# schematic.net
KiCad netlist of a schematic drawn in EasyEDA
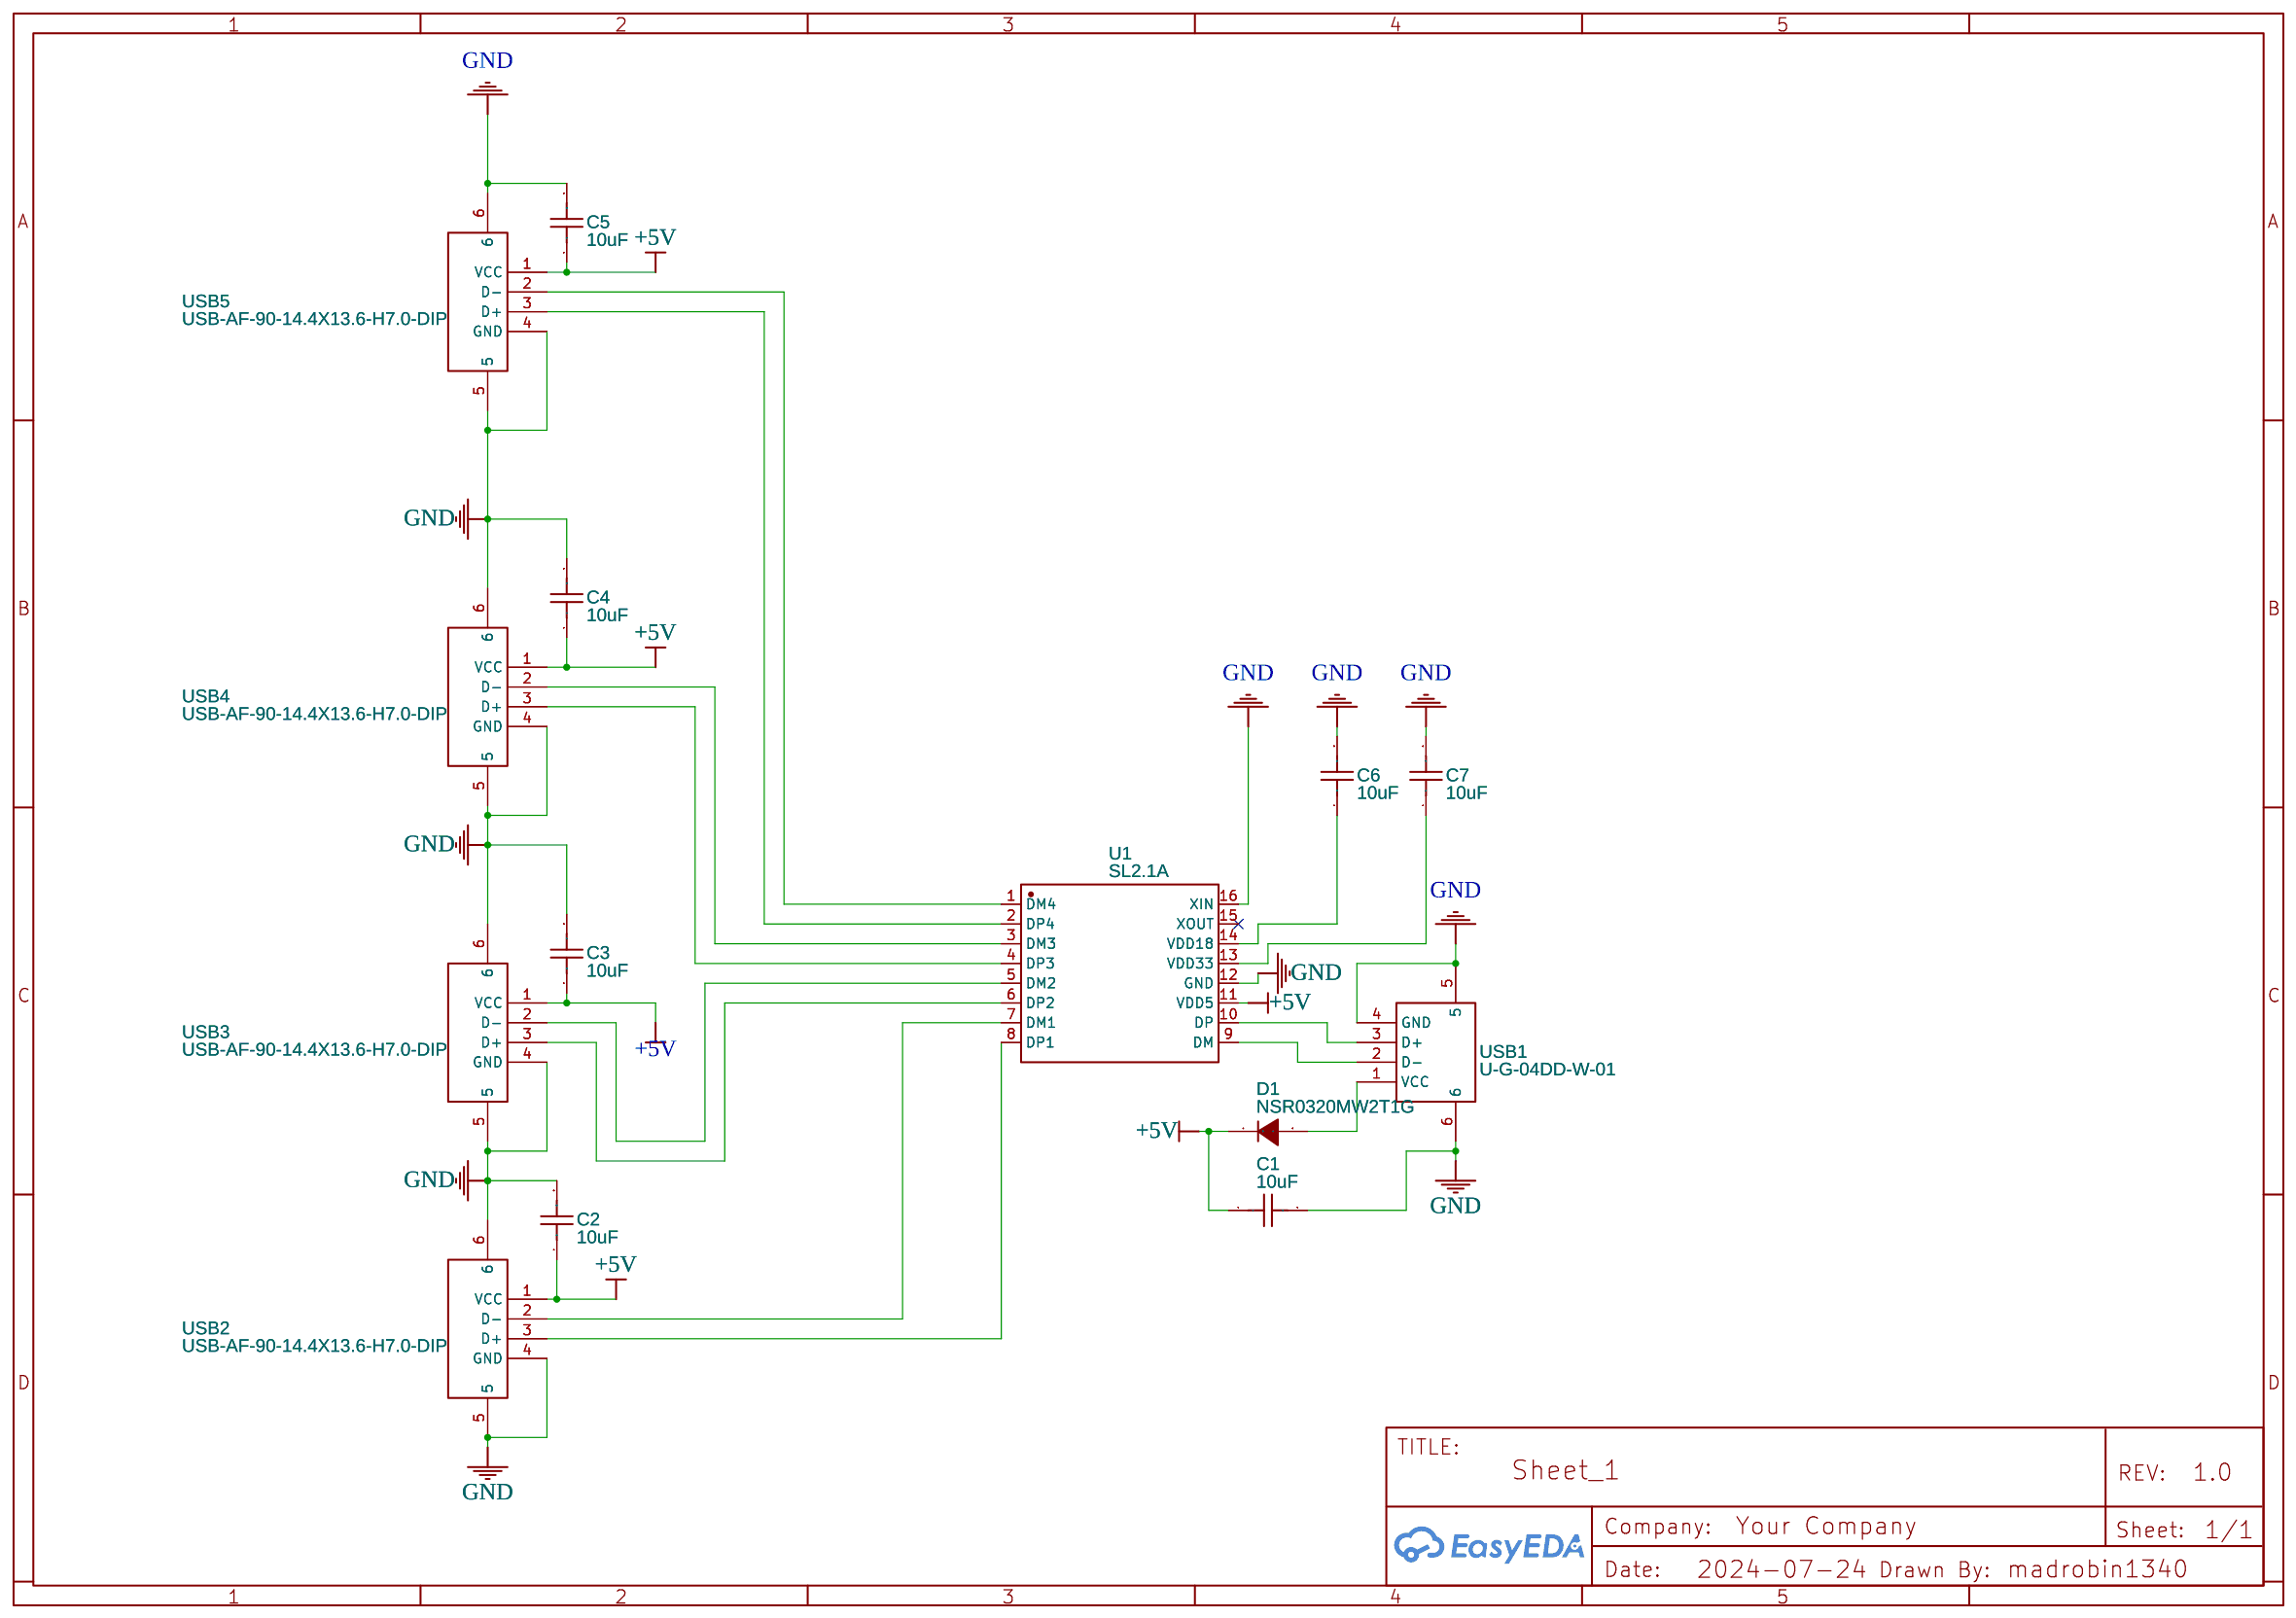
[diagram p0: schematic sheet]

(export (version "E")
  (design (tool "Eeschema 10.0.6"))
  (components
    (comp (ref "C1")
      (value "10uF")
      (fields
        (field (name "Manufacturer Part") "CL10A106KP8NNNC")
        (field (name "Manufacturer") "SAMSUNG(三星)")
      )
      (libsource (lib "") (part "CL10A106KP8NNNC_1"))
    )
    (comp (ref "C2")
      (value "10uF")
      (fields
        (field (name "Manufacturer Part") "CL10A106KP8NNNC")
        (field (name "Manufacturer") "SAMSUNG(三星)")
      )
      (libsource (lib "") (part "CL10A106KP8NNNC"))
    )
    (comp (ref "C3")
      (value "10uF")
      (fields
        (field (name "Manufacturer Part") "CL10A106KP8NNNC")
        (field (name "Manufacturer") "SAMSUNG(三星)")
      )
      (libsource (lib "") (part "CL10A106KP8NNNC"))
    )
    (comp (ref "C4")
      (value "10uF")
      (fields
        (field (name "Manufacturer Part") "CL10A106KP8NNNC")
        (field (name "Manufacturer") "SAMSUNG(三星)")
      )
      (libsource (lib "") (part "CL10A106KP8NNNC"))
    )
    (comp (ref "C5")
      (value "10uF")
      (fields
        (field (name "Manufacturer Part") "CL10A106KP8NNNC")
        (field (name "Manufacturer") "SAMSUNG(三星)")
      )
      (libsource (lib "") (part "CL10A106KP8NNNC"))
    )
    (comp (ref "C6")
      (value "10uF")
      (fields
        (field (name "Manufacturer Part") "CL10A106KP8NNNC")
        (field (name "Manufacturer") "SAMSUNG(三星)")
      )
      (libsource (lib "") (part "CL10A106KP8NNNC"))
    )
    (comp (ref "C7")
      (value "10uF")
      (fields
        (field (name "Manufacturer Part") "CL10A106KP8NNNC")
        (field (name "Manufacturer") "SAMSUNG(三星)")
      )
      (libsource (lib "") (part "CL10A106KP8NNNC"))
    )
    (comp (ref "D1")
      (value "NSR0320MW2T1G")
      (fields (field (name "Manufacturer") "onsemi(安森美)"))
      (libsource (lib "") (part "NSR0320MW2T1G"))
    )
    (comp (ref "U1")
      (value "SL2.1A")
      (fields (field (name "Manufacturer") "CoreChips(和芯润德)"))
      (libsource (lib "") (part "SL2.1A"))
    )
    (comp (ref "USB1")
      (value "U-G-04DD-W-01")
      (fields (field (name "Manufacturer Part") "U-G-O4DD-W-1") (field (name "Manufacturer") "韩国韩荣"))
      (libsource (lib "") (part "U-G-04DD-W-01"))
    )
    (comp (ref "USB2")
      (value "USB-AF-90-14.4X13.6-H7.0-DIP")
      (fields (field (name "Manufacturer Part") "903-131A1011D10100") (field (name "Manufacturer") "精拓金"))
      (libsource (lib "") (part "USB-AF-90-14.4X13.6-H7.0-DIP"))
    )
    (comp (ref "USB3")
      (value "USB-AF-90-14.4X13.6-H7.0-DIP")
      (fields (field (name "Manufacturer Part") "903-131A1011D10100") (field (name "Manufacturer") "精拓金"))
      (libsource (lib "") (part "USB-AF-90-14.4X13.6-H7.0-DIP"))
    )
    (comp (ref "USB4")
      (value "USB-AF-90-14.4X13.6-H7.0-DIP")
      (fields (field (name "Manufacturer Part") "903-131A1011D10100") (field (name "Manufacturer") "精拓金"))
      (libsource (lib "") (part "USB-AF-90-14.4X13.6-H7.0-DIP"))
    )
    (comp (ref "USB5")
      (value "USB-AF-90-14.4X13.6-H7.0-DIP")
      (fields (field (name "Manufacturer Part") "903-131A1011D10100") (field (name "Manufacturer") "精拓金"))
      (libsource (lib "") (part "USB-AF-90-14.4X13.6-H7.0-DIP"))
    )
  )
  (nets
    (net (code "1") (name "+5V") (class "Default")
      (node (ref "C1") (pin "1") (pinfunction "1_1") (pintype "unspecified"))
      (node (ref "C2") (pin "1") (pinfunction "1_1") (pintype "unspecified"))
      (node (ref "C3") (pin "1") (pinfunction "1_1") (pintype "unspecified"))
      (node (ref "C4") (pin "1") (pinfunction "1_1") (pintype "unspecified"))
      (node (ref "C5") (pin "1") (pinfunction "1_1") (pintype "unspecified"))
      (node (ref "D1") (pin "1") (pinfunction "C_1") (pintype "unspecified"))
      (node (ref "U1") (pin "11") (pinfunction "VDD5_11") (pintype "unspecified"))
      (node (ref "USB2") (pin "1") (pinfunction "VCC_1") (pintype "unspecified"))
      (node (ref "USB3") (pin "1") (pinfunction "VCC_1") (pintype "unspecified"))
      (node (ref "USB4") (pin "1") (pinfunction "VCC_1") (pintype "unspecified"))
      (node (ref "USB5") (pin "1") (pinfunction "VCC_1") (pintype "unspecified"))
    )
    (net (code "2") (name "GND") (class "Default")
      (node (ref "C1") (pin "2") (pinfunction "2_2") (pintype "unspecified"))
      (node (ref "C2") (pin "2") (pinfunction "2_2") (pintype "unspecified"))
      (node (ref "C3") (pin "2") (pinfunction "2_2") (pintype "unspecified"))
      (node (ref "C4") (pin "2") (pinfunction "2_2") (pintype "unspecified"))
      (node (ref "C5") (pin "2") (pinfunction "2_2") (pintype "unspecified"))
      (node (ref "C6") (pin "2") (pinfunction "2_2") (pintype "unspecified"))
      (node (ref "C7") (pin "2") (pinfunction "2_2") (pintype "unspecified"))
      (node (ref "U1") (pin "12") (pinfunction "GND_12") (pintype "unspecified"))
      (node (ref "U1") (pin "16") (pinfunction "XIN_16") (pintype "unspecified"))
      (node (ref "USB1") (pin "4") (pinfunction "GND_4") (pintype "unspecified"))
      (node (ref "USB1") (pin "5") (pinfunction "5_5") (pintype "unspecified"))
      (node (ref "USB1") (pin "6") (pinfunction "6_6") (pintype "unspecified"))
      (node (ref "USB2") (pin "4") (pinfunction "GND_4") (pintype "unspecified"))
      (node (ref "USB2") (pin "5") (pinfunction "5_5") (pintype "unspecified"))
      (node (ref "USB2") (pin "6") (pinfunction "6_6") (pintype "unspecified"))
      (node (ref "USB3") (pin "4") (pinfunction "GND_4") (pintype "unspecified"))
      (node (ref "USB3") (pin "5") (pinfunction "5_5") (pintype "unspecified"))
      (node (ref "USB3") (pin "6") (pinfunction "6_6") (pintype "unspecified"))
      (node (ref "USB4") (pin "4") (pinfunction "GND_4") (pintype "unspecified"))
      (node (ref "USB4") (pin "5") (pinfunction "5_5") (pintype "unspecified"))
      (node (ref "USB4") (pin "6") (pinfunction "6_6") (pintype "unspecified"))
      (node (ref "USB5") (pin "4") (pinfunction "GND_4") (pintype "unspecified"))
      (node (ref "USB5") (pin "5") (pinfunction "5_5") (pintype "unspecified"))
      (node (ref "USB5") (pin "6") (pinfunction "6_6") (pintype "unspecified"))
    )
    (net (code "3") (name "Net-(D1-A)") (class "Default")
      (node (ref "D1") (pin "2") (pinfunction "A_2") (pintype "unspecified"))
      (node (ref "USB1") (pin "1") (pinfunction "VCC_1") (pintype "unspecified"))
    )
    (net (code "4") (name "Net-(U1-DM)") (class "Default")
      (node (ref "U1") (pin "9") (pinfunction "DM_9") (pintype "unspecified"))
      (node (ref "USB1") (pin "2") (pinfunction "D-_2") (pintype "unspecified"))
    )
    (net (code "5") (name "Net-(U1-DM1)") (class "Default")
      (node (ref "U1") (pin "7") (pinfunction "DM1_7") (pintype "unspecified"))
      (node (ref "USB2") (pin "2") (pinfunction "D-_2") (pintype "unspecified"))
    )
    (net (code "6") (name "Net-(U1-DM2)") (class "Default")
      (node (ref "U1") (pin "5") (pinfunction "DM2_5") (pintype "unspecified"))
      (node (ref "USB3") (pin "2") (pinfunction "D-_2") (pintype "unspecified"))
    )
    (net (code "7") (name "Net-(U1-DM3)") (class "Default")
      (node (ref "U1") (pin "3") (pinfunction "DM3_3") (pintype "unspecified"))
      (node (ref "USB4") (pin "2") (pinfunction "D-_2") (pintype "unspecified"))
    )
    (net (code "8") (name "Net-(U1-DM4)") (class "Default")
      (node (ref "U1") (pin "1") (pinfunction "DM4_1") (pintype "unspecified"))
      (node (ref "USB5") (pin "2") (pinfunction "D-_2") (pintype "unspecified"))
    )
    (net (code "9") (name "Net-(U1-DP)") (class "Default")
      (node (ref "U1") (pin "10") (pinfunction "DP_10") (pintype "unspecified"))
      (node (ref "USB1") (pin "3") (pinfunction "D+_3") (pintype "unspecified"))
    )
    (net (code "10") (name "Net-(U1-DP1)") (class "Default")
      (node (ref "U1") (pin "8") (pinfunction "DP1_8") (pintype "unspecified"))
      (node (ref "USB2") (pin "3") (pinfunction "D+_3") (pintype "unspecified"))
    )
    (net (code "11") (name "Net-(U1-DP2)") (class "Default")
      (node (ref "U1") (pin "6") (pinfunction "DP2_6") (pintype "unspecified"))
      (node (ref "USB3") (pin "3") (pinfunction "D+_3") (pintype "unspecified"))
    )
    (net (code "12") (name "Net-(U1-DP3)") (class "Default")
      (node (ref "U1") (pin "4") (pinfunction "DP3_4") (pintype "unspecified"))
      (node (ref "USB4") (pin "3") (pinfunction "D+_3") (pintype "unspecified"))
    )
    (net (code "13") (name "Net-(U1-DP4)") (class "Default")
      (node (ref "U1") (pin "2") (pinfunction "DP4_2") (pintype "unspecified"))
      (node (ref "USB5") (pin "3") (pinfunction "D+_3") (pintype "unspecified"))
    )
    (net (code "14") (name "Net-(U1-VDD18)") (class "Default")
      (node (ref "C6") (pin "1") (pinfunction "1_1") (pintype "unspecified"))
      (node (ref "U1") (pin "14") (pinfunction "VDD18_14") (pintype "unspecified"))
    )
    (net (code "15") (name "Net-(U1-VDD33)") (class "Default")
      (node (ref "C7") (pin "1") (pinfunction "1_1") (pintype "unspecified"))
      (node (ref "U1") (pin "13") (pinfunction "VDD33_13") (pintype "unspecified"))
    )
    (net (code "16") (name "unconnected-(U1-XOUT-Pad15)") (class "Default")
      (node (ref "U1") (pin "15") (pinfunction "XOUT_15") (pintype "unspecified+no_connect"))
    )
  )
)
